# Display.net
KiCad netlist of a schematic drawn in Altium Designer
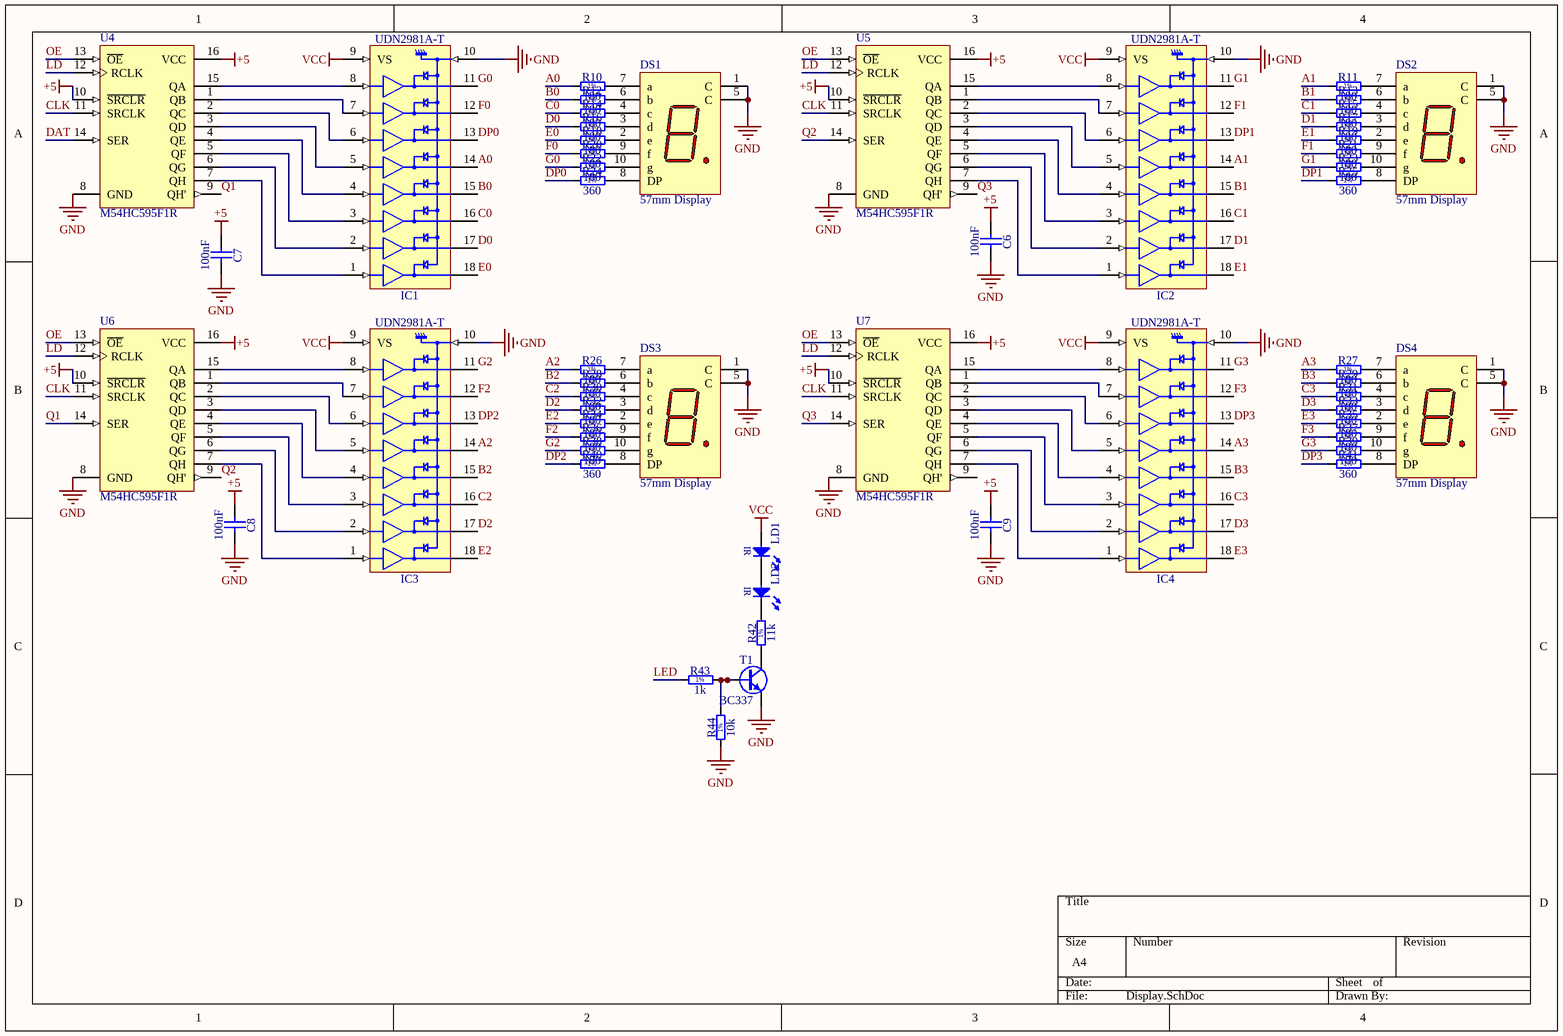
[diagram p0: Display.SchDoc]

(export (version "E")
  (design (tool "Eeschema 10.0.6"))
  (components
    (comp (ref "C6")
      (value "100nF")
      (footprint "CAPRR508-350X500X500")
      (description "Non-polarised capacitor")
      (fields
        (field (name "PART NUMBER") "CCR_100NF_50V_10%_X7R_508-350X500X500")
        (field (name "VOLTAGE") "50VDC")
        (field (name "AUTHOR") "CERN DEM JLC")
      )
      (libsource (lib "Capacitors") (part "Capacitor - non polarized"))
    )
    (comp (ref "C7")
      (value "100nF")
      (footprint "CAPRR508-350X500X500")
      (description "Non-polarised capacitor")
      (fields
        (field (name "PART NUMBER") "CCR_100NF_50V_10%_X7R_508-350X500X500")
        (field (name "VOLTAGE") "50VDC")
        (field (name "AUTHOR") "CERN DEM JLC")
      )
      (libsource (lib "Capacitors") (part "Capacitor - non polarized"))
    )
    (comp (ref "C8")
      (value "100nF")
      (footprint "CAPRR508-350X500X500")
      (description "Non-polarised capacitor")
      (fields
        (field (name "PART NUMBER") "CCR_100NF_50V_10%_X7R_508-350X500X500")
        (field (name "VOLTAGE") "50VDC")
        (field (name "AUTHOR") "CERN DEM JLC")
      )
      (libsource (lib "Capacitors") (part "Capacitor - non polarized"))
    )
    (comp (ref "C9")
      (value "100nF")
      (footprint "CAPRR508-350X500X500")
      (description "Non-polarised capacitor")
      (fields
        (field (name "PART NUMBER") "CCR_100NF_50V_10%_X7R_508-350X500X500")
        (field (name "VOLTAGE") "50VDC")
        (field (name "AUTHOR") "CERN DEM JLC")
      )
      (libsource (lib "Capacitors") (part "Capacitor - non polarized"))
    )
    (comp (ref "DS1")
      (value "57mm Display")
      (footprint "57mm 7 Segment")
      (libsource (lib "Tansa_Server_Schematic_Library") (part "57mm 2.3{dblquote} Display"))
    )
    (comp (ref "DS2")
      (value "57mm Display")
      (footprint "57mm 7 Segment")
      (libsource (lib "Tansa_Server_Schematic_Library") (part "57mm 2.3{dblquote} Display"))
    )
    (comp (ref "DS3")
      (value "57mm Display")
      (footprint "57mm 7 Segment")
      (libsource (lib "Tansa_Server_Schematic_Library") (part "57mm 2.3{dblquote} Display"))
    )
    (comp (ref "DS4")
      (value "57mm Display")
      (footprint "57mm 7 Segment")
      (libsource (lib "Tansa_Server_Schematic_Library") (part "57mm 2.3{dblquote} Display"))
    )
    (comp (ref "IC1")
      (value "UDN2981A-T")
      (footprint "DIP18-300")
      (description "8-Channel Source Drivers")
      (fields (field (name "MANUFACTURER") "ALLEGRO MICROSYSTEM") (field (name "AUTHOR") "CERN DEM JLC"))
      (libsource (lib "ICs And Semiconductors") (part "UDN2981"))
    )
    (comp (ref "IC2")
      (value "UDN2981A-T")
      (footprint "DIP18-300")
      (description "8-Channel Source Drivers")
      (fields (field (name "MANUFACTURER") "ALLEGRO MICROSYSTEM") (field (name "AUTHOR") "CERN DEM JLC"))
      (libsource (lib "ICs And Semiconductors") (part "UDN2981"))
    )
    (comp (ref "IC3")
      (value "UDN2981A-T")
      (footprint "DIP18-300")
      (description "8-Channel Source Drivers")
      (fields (field (name "MANUFACTURER") "ALLEGRO MICROSYSTEM") (field (name "AUTHOR") "CERN DEM JLC"))
      (libsource (lib "ICs And Semiconductors") (part "UDN2981"))
    )
    (comp (ref "IC4")
      (value "UDN2981A-T")
      (footprint "DIP18-300")
      (description "8-Channel Source Drivers")
      (fields (field (name "MANUFACTURER") "ALLEGRO MICROSYSTEM") (field (name "AUTHOR") "CERN DEM JLC"))
      (libsource (lib "ICs And Semiconductors") (part "UDN2981"))
    )
    (comp (ref "LD1")
      (value "IR")
      (footprint "LED_VISHAY_TSAL6200")
      (description "LED Infrared Emitting Diode 1C 2A")
      (fields
        (field (name "PART NUMBER") "LED_VISHAY_TSAL6200")
        (field (name "MANUFACTURER") "VISHAY SEMICONDUCTORS")
        (field (name "AUTHOR") "CERN DEM JMW")
      )
      (libsource (lib "ICs And Semiconductors") (part "LED IR 1C 2A"))
    )
    (comp (ref "LD2")
      (value "IR")
      (footprint "LED_VISHAY_TSAL6200")
      (description "LED Infrared Emitting Diode 1C 2A")
      (fields
        (field (name "PART NUMBER") "LED_VISHAY_TSAL6200")
        (field (name "MANUFACTURER") "VISHAY SEMICONDUCTORS")
        (field (name "AUTHOR") "CERN DEM JMW")
      )
      (libsource (lib "ICs And Semiconductors") (part "LED IR 1C 2A"))
    )
    (comp (ref "R10")
      (value "180")
      (footprint "RES1016-630X250")
      (description "Resistor - 1%")
      (fields
        (field (name "PART NUMBER") "RMF_180R_1%_0.6W_50PPM_1016-630X250")
        (field (name "POWER") "0.6W")
        (field (name "AUTHOR") "CERN DEM JLC")
      )
      (libsource (lib "Resistors") (part "Resistor - 1%"))
    )
    (comp (ref "R11")
      (value "180")
      (footprint "RES1016-630X250")
      (description "Resistor - 1%")
      (fields
        (field (name "PART NUMBER") "RMF_180R_1%_0.6W_50PPM_1016-630X250")
        (field (name "POWER") "0.6W")
        (field (name "AUTHOR") "CERN DEM JLC")
      )
      (libsource (lib "Resistors") (part "Resistor - 1%"))
    )
    (comp (ref "R12")
      (value "180")
      (footprint "RES1016-630X250")
      (description "Resistor - 1%")
      (fields
        (field (name "PART NUMBER") "RMF_180R_1%_0.6W_50PPM_1016-630X250")
        (field (name "POWER") "0.6W")
        (field (name "AUTHOR") "CERN DEM JLC")
      )
      (libsource (lib "Resistors") (part "Resistor - 1%"))
    )
    (comp (ref "R13")
      (value "180")
      (footprint "RES1016-630X250")
      (description "Resistor - 1%")
      (fields
        (field (name "PART NUMBER") "RMF_180R_1%_0.6W_50PPM_1016-630X250")
        (field (name "POWER") "0.6W")
        (field (name "AUTHOR") "CERN DEM JLC")
      )
      (libsource (lib "Resistors") (part "Resistor - 1%"))
    )
    (comp (ref "R14")
      (value "180")
      (footprint "RES1016-630X250")
      (description "Resistor - 1%")
      (fields
        (field (name "PART NUMBER") "RMF_180R_1%_0.6W_50PPM_1016-630X250")
        (field (name "POWER") "0.6W")
        (field (name "AUTHOR") "CERN DEM JLC")
      )
      (libsource (lib "Resistors") (part "Resistor - 1%"))
    )
    (comp (ref "R15")
      (value "180")
      (footprint "RES1016-630X250")
      (description "Resistor - 1%")
      (fields
        (field (name "PART NUMBER") "RMF_180R_1%_0.6W_50PPM_1016-630X250")
        (field (name "POWER") "0.6W")
        (field (name "AUTHOR") "CERN DEM JLC")
      )
      (libsource (lib "Resistors") (part "Resistor - 1%"))
    )
    (comp (ref "R16")
      (value "180")
      (footprint "RES1016-630X250")
      (description "Resistor - 1%")
      (fields
        (field (name "PART NUMBER") "RMF_180R_1%_0.6W_50PPM_1016-630X250")
        (field (name "POWER") "0.6W")
        (field (name "AUTHOR") "CERN DEM JLC")
      )
      (libsource (lib "Resistors") (part "Resistor - 1%"))
    )
    (comp (ref "R17")
      (value "180")
      (footprint "RES1016-630X250")
      (description "Resistor - 1%")
      (fields
        (field (name "PART NUMBER") "RMF_180R_1%_0.6W_50PPM_1016-630X250")
        (field (name "POWER") "0.6W")
        (field (name "AUTHOR") "CERN DEM JLC")
      )
      (libsource (lib "Resistors") (part "Resistor - 1%"))
    )
    (comp (ref "R18")
      (value "180")
      (footprint "RES1016-630X250")
      (description "Resistor - 1%")
      (fields
        (field (name "PART NUMBER") "RMF_180R_1%_0.6W_50PPM_1016-630X250")
        (field (name "POWER") "0.6W")
        (field (name "AUTHOR") "CERN DEM JLC")
      )
      (libsource (lib "Resistors") (part "Resistor - 1%"))
    )
    (comp (ref "R19")
      (value "180")
      (footprint "RES1016-630X250")
      (description "Resistor - 1%")
      (fields
        (field (name "PART NUMBER") "RMF_180R_1%_0.6W_50PPM_1016-630X250")
        (field (name "POWER") "0.6W")
        (field (name "AUTHOR") "CERN DEM JLC")
      )
      (libsource (lib "Resistors") (part "Resistor - 1%"))
    )
    (comp (ref "R20")
      (value "180")
      (footprint "RES1016-630X250")
      (description "Resistor - 1%")
      (fields
        (field (name "PART NUMBER") "RMF_180R_1%_0.6W_50PPM_1016-630X250")
        (field (name "POWER") "0.6W")
        (field (name "AUTHOR") "CERN DEM JLC")
      )
      (libsource (lib "Resistors") (part "Resistor - 1%"))
    )
    (comp (ref "R21")
      (value "180")
      (footprint "RES1016-630X250")
      (description "Resistor - 1%")
      (fields
        (field (name "PART NUMBER") "RMF_180R_1%_0.6W_50PPM_1016-630X250")
        (field (name "POWER") "0.6W")
        (field (name "AUTHOR") "CERN DEM JLC")
      )
      (libsource (lib "Resistors") (part "Resistor - 1%"))
    )
    (comp (ref "R22")
      (value "180")
      (footprint "RES1016-630X250")
      (description "Resistor - 1%")
      (fields
        (field (name "PART NUMBER") "RMF_180R_1%_0.6W_50PPM_1016-630X250")
        (field (name "POWER") "0.6W")
        (field (name "AUTHOR") "CERN DEM JLC")
      )
      (libsource (lib "Resistors") (part "Resistor - 1%"))
    )
    (comp (ref "R23")
      (value "180")
      (footprint "RES1016-630X250")
      (description "Resistor - 1%")
      (fields
        (field (name "PART NUMBER") "RMF_180R_1%_0.6W_50PPM_1016-630X250")
        (field (name "POWER") "0.6W")
        (field (name "AUTHOR") "CERN DEM JLC")
      )
      (libsource (lib "Resistors") (part "Resistor - 1%"))
    )
    (comp (ref "R24")
      (value "360")
      (footprint "RES1016-630X250")
      (description "Resistor - 1%")
      (fields
        (field (name "PART NUMBER") "RMF_360R_1%_0.6W_50PPM_1016-630X250")
        (field (name "POWER") "0.6W")
        (field (name "AUTHOR") "CERN DEM JLC")
      )
      (libsource (lib "Resistors") (part "Resistor - 1%"))
    )
    (comp (ref "R25")
      (value "360")
      (footprint "RES1016-630X250")
      (description "Resistor - 1%")
      (fields
        (field (name "PART NUMBER") "RMF_360R_1%_0.6W_50PPM_1016-630X250")
        (field (name "POWER") "0.6W")
        (field (name "AUTHOR") "CERN DEM JLC")
      )
      (libsource (lib "Resistors") (part "Resistor - 1%"))
    )
    (comp (ref "R26")
      (value "180")
      (footprint "RES1016-630X250")
      (description "Resistor - 1%")
      (fields
        (field (name "PART NUMBER") "RMF_180R_1%_0.6W_50PPM_1016-630X250")
        (field (name "POWER") "0.6W")
        (field (name "AUTHOR") "CERN DEM JLC")
      )
      (libsource (lib "Resistors") (part "Resistor - 1%"))
    )
    (comp (ref "R27")
      (value "180")
      (footprint "RES1016-630X250")
      (description "Resistor - 1%")
      (fields
        (field (name "PART NUMBER") "RMF_180R_1%_0.6W_50PPM_1016-630X250")
        (field (name "POWER") "0.6W")
        (field (name "AUTHOR") "CERN DEM JLC")
      )
      (libsource (lib "Resistors") (part "Resistor - 1%"))
    )
    (comp (ref "R28")
      (value "180")
      (footprint "RES1016-630X250")
      (description "Resistor - 1%")
      (fields
        (field (name "PART NUMBER") "RMF_180R_1%_0.6W_50PPM_1016-630X250")
        (field (name "POWER") "0.6W")
        (field (name "AUTHOR") "CERN DEM JLC")
      )
      (libsource (lib "Resistors") (part "Resistor - 1%"))
    )
    (comp (ref "R29")
      (value "180")
      (footprint "RES1016-630X250")
      (description "Resistor - 1%")
      (fields
        (field (name "PART NUMBER") "RMF_180R_1%_0.6W_50PPM_1016-630X250")
        (field (name "POWER") "0.6W")
        (field (name "AUTHOR") "CERN DEM JLC")
      )
      (libsource (lib "Resistors") (part "Resistor - 1%"))
    )
    (comp (ref "R30")
      (value "180")
      (footprint "RES1016-630X250")
      (description "Resistor - 1%")
      (fields
        (field (name "PART NUMBER") "RMF_180R_1%_0.6W_50PPM_1016-630X250")
        (field (name "POWER") "0.6W")
        (field (name "AUTHOR") "CERN DEM JLC")
      )
      (libsource (lib "Resistors") (part "Resistor - 1%"))
    )
    (comp (ref "R31")
      (value "180")
      (footprint "RES1016-630X250")
      (description "Resistor - 1%")
      (fields
        (field (name "PART NUMBER") "RMF_180R_1%_0.6W_50PPM_1016-630X250")
        (field (name "POWER") "0.6W")
        (field (name "AUTHOR") "CERN DEM JLC")
      )
      (libsource (lib "Resistors") (part "Resistor - 1%"))
    )
    (comp (ref "R32")
      (value "180")
      (footprint "RES1016-630X250")
      (description "Resistor - 1%")
      (fields
        (field (name "PART NUMBER") "RMF_180R_1%_0.6W_50PPM_1016-630X250")
        (field (name "POWER") "0.6W")
        (field (name "AUTHOR") "CERN DEM JLC")
      )
      (libsource (lib "Resistors") (part "Resistor - 1%"))
    )
    (comp (ref "R33")
      (value "180")
      (footprint "RES1016-630X250")
      (description "Resistor - 1%")
      (fields
        (field (name "PART NUMBER") "RMF_180R_1%_0.6W_50PPM_1016-630X250")
        (field (name "POWER") "0.6W")
        (field (name "AUTHOR") "CERN DEM JLC")
      )
      (libsource (lib "Resistors") (part "Resistor - 1%"))
    )
    (comp (ref "R34")
      (value "180")
      (footprint "RES1016-630X250")
      (description "Resistor - 1%")
      (fields
        (field (name "PART NUMBER") "RMF_180R_1%_0.6W_50PPM_1016-630X250")
        (field (name "POWER") "0.6W")
        (field (name "AUTHOR") "CERN DEM JLC")
      )
      (libsource (lib "Resistors") (part "Resistor - 1%"))
    )
    (comp (ref "R35")
      (value "180")
      (footprint "RES1016-630X250")
      (description "Resistor - 1%")
      (fields
        (field (name "PART NUMBER") "RMF_180R_1%_0.6W_50PPM_1016-630X250")
        (field (name "POWER") "0.6W")
        (field (name "AUTHOR") "CERN DEM JLC")
      )
      (libsource (lib "Resistors") (part "Resistor - 1%"))
    )
    (comp (ref "R36")
      (value "180")
      (footprint "RES1016-630X250")
      (description "Resistor - 1%")
      (fields
        (field (name "PART NUMBER") "RMF_180R_1%_0.6W_50PPM_1016-630X250")
        (field (name "POWER") "0.6W")
        (field (name "AUTHOR") "CERN DEM JLC")
      )
      (libsource (lib "Resistors") (part "Resistor - 1%"))
    )
    (comp (ref "R37")
      (value "180")
      (footprint "RES1016-630X250")
      (description "Resistor - 1%")
      (fields
        (field (name "PART NUMBER") "RMF_180R_1%_0.6W_50PPM_1016-630X250")
        (field (name "POWER") "0.6W")
        (field (name "AUTHOR") "CERN DEM JLC")
      )
      (libsource (lib "Resistors") (part "Resistor - 1%"))
    )
    (comp (ref "R38")
      (value "180")
      (footprint "RES1016-630X250")
      (description "Resistor - 1%")
      (fields
        (field (name "PART NUMBER") "RMF_180R_1%_0.6W_50PPM_1016-630X250")
        (field (name "POWER") "0.6W")
        (field (name "AUTHOR") "CERN DEM JLC")
      )
      (libsource (lib "Resistors") (part "Resistor - 1%"))
    )
    (comp (ref "R39")
      (value "180")
      (footprint "RES1016-630X250")
      (description "Resistor - 1%")
      (fields
        (field (name "PART NUMBER") "RMF_180R_1%_0.6W_50PPM_1016-630X250")
        (field (name "POWER") "0.6W")
        (field (name "AUTHOR") "CERN DEM JLC")
      )
      (libsource (lib "Resistors") (part "Resistor - 1%"))
    )
    (comp (ref "R40")
      (value "360")
      (footprint "RES1016-630X250")
      (description "Resistor - 1%")
      (fields
        (field (name "PART NUMBER") "RMF_360R_1%_0.6W_50PPM_1016-630X250")
        (field (name "POWER") "0.6W")
        (field (name "AUTHOR") "CERN DEM JLC")
      )
      (libsource (lib "Resistors") (part "Resistor - 1%"))
    )
    (comp (ref "R41")
      (value "360")
      (footprint "RES1016-630X250")
      (description "Resistor - 1%")
      (fields
        (field (name "PART NUMBER") "RMF_360R_1%_0.6W_50PPM_1016-630X250")
        (field (name "POWER") "0.6W")
        (field (name "AUTHOR") "CERN DEM JLC")
      )
      (libsource (lib "Resistors") (part "Resistor - 1%"))
    )
    (comp (ref "R42")
      (value "11k")
      (footprint "RES1016-630X250")
      (description "Resistor - 1%")
      (fields
        (field (name "PART NUMBER") "RMF_11K_1%_0.6W_50PPM_1016-630X250")
        (field (name "POWER") "0.6W")
        (field (name "AUTHOR") "CERN DEM JLC")
      )
      (libsource (lib "Resistors") (part "Resistor - 1%"))
    )
    (comp (ref "R43")
      (value "1k")
      (footprint "RES1016-630X250")
      (description "Resistor - 1%")
      (fields
        (field (name "PART NUMBER") "RMF_1K_1%_0.6W_50PPM_1016-630X250")
        (field (name "POWER") "0.6W")
        (field (name "AUTHOR") "CERN DEM JLC")
      )
      (libsource (lib "Resistors") (part "Resistor - 1%"))
    )
    (comp (ref "R44")
      (value "10k")
      (footprint "RES1016-630X250")
      (description "Resistor - 1%")
      (fields
        (field (name "PART NUMBER") "RMF_10K_1%_0.6W_50PPM_1016-630X250")
        (field (name "POWER") "0.6W")
        (field (name "AUTHOR") "CERN DEM JLC")
      )
      (libsource (lib "Resistors") (part "Resistor - 1%"))
    )
    (comp (ref "T1")
      (value "BC337")
      (footprint "TO-92AA-P254")
      (description "NPN Transistor")
      (fields (field (name "MANUFACTURER") "FAIRCHILD SEMICONDUCTOR") (field (name "AUTHOR") "CERN DEM JLC"))
      (libsource (lib "ICs And Semiconductors") (part "NPN C1 B2 E3"))
    )
    (comp (ref "U4")
      (value "M54HC595F1R")
      (footprint "DIP16")
      (description "8 Bit Shift Register with Output Latches (3 STATE)")
      (fields (field (name "PUBLISHER") "Altium Limited"))
      (libsource (lib "ST Logic Register") (part "M54HC595F1R"))
    )
    (comp (ref "U5")
      (value "M54HC595F1R")
      (footprint "DIP16")
      (description "8 Bit Shift Register with Output Latches (3 STATE)")
      (fields (field (name "PUBLISHER") "Altium Limited"))
      (libsource (lib "ST Logic Register") (part "M54HC595F1R"))
    )
    (comp (ref "U6")
      (value "M54HC595F1R")
      (footprint "DIP16")
      (description "8 Bit Shift Register with Output Latches (3 STATE)")
      (fields (field (name "PUBLISHER") "Altium Limited"))
      (libsource (lib "ST Logic Register") (part "M54HC595F1R"))
    )
    (comp (ref "U7")
      (value "M54HC595F1R")
      (footprint "DIP16")
      (description "8 Bit Shift Register with Output Latches (3 STATE)")
      (fields (field (name "PUBLISHER") "Altium Limited"))
      (libsource (lib "ST Logic Register") (part "M54HC595F1R"))
    )
  )
  (nets
    (net (code "1") (name "+5") (class "Default")
      (node (ref "C6") (pin "1") (pinfunction "1_1") (pintype "passive"))
      (node (ref "C7") (pin "1") (pinfunction "1_1") (pintype "passive"))
      (node (ref "C8") (pin "1") (pinfunction "1_1") (pintype "passive"))
      (node (ref "C9") (pin "1") (pinfunction "1_1") (pintype "passive"))
      (node (ref "U4") (pin "10") (pinfunction "~{SRCLR}_10") (pintype "input"))
      (node (ref "U4") (pin "16") (pinfunction "VCC_16") (pintype "power_in"))
      (node (ref "U5") (pin "10") (pinfunction "~{SRCLR}_10") (pintype "input"))
      (node (ref "U5") (pin "16") (pinfunction "VCC_16") (pintype "power_in"))
      (node (ref "U6") (pin "10") (pinfunction "~{SRCLR}_10") (pintype "input"))
      (node (ref "U6") (pin "16") (pinfunction "VCC_16") (pintype "power_in"))
      (node (ref "U7") (pin "10") (pinfunction "~{SRCLR}_10") (pintype "input"))
      (node (ref "U7") (pin "16") (pinfunction "VCC_16") (pintype "power_in"))
    )
    (net (code "2") (name "/A0") (class "Default")
      (node (ref "IC1") (pin "14") (pinfunction "O5_14") (pintype "open_collector"))
      (node (ref "R10") (pin "1") (pinfunction "1_1") (pintype "passive"))
    )
    (net (code "3") (name "/A1") (class "Default")
      (node (ref "IC2") (pin "14") (pinfunction "O5_14") (pintype "open_collector"))
      (node (ref "R11") (pin "1") (pinfunction "1_1") (pintype "passive"))
    )
    (net (code "4") (name "/A2") (class "Default")
      (node (ref "IC3") (pin "14") (pinfunction "O5_14") (pintype "open_collector"))
      (node (ref "R26") (pin "1") (pinfunction "1_1") (pintype "passive"))
    )
    (net (code "5") (name "/A3") (class "Default")
      (node (ref "IC4") (pin "14") (pinfunction "O5_14") (pintype "open_collector"))
      (node (ref "R27") (pin "1") (pinfunction "1_1") (pintype "passive"))
    )
    (net (code "6") (name "/B0") (class "Default")
      (node (ref "IC1") (pin "15") (pinfunction "O4_15") (pintype "open_collector"))
      (node (ref "R12") (pin "1") (pinfunction "1_1") (pintype "passive"))
    )
    (net (code "7") (name "/B1") (class "Default")
      (node (ref "IC2") (pin "15") (pinfunction "O4_15") (pintype "open_collector"))
      (node (ref "R13") (pin "1") (pinfunction "1_1") (pintype "passive"))
    )
    (net (code "8") (name "/B2") (class "Default")
      (node (ref "IC3") (pin "15") (pinfunction "O4_15") (pintype "open_collector"))
      (node (ref "R28") (pin "1") (pinfunction "1_1") (pintype "passive"))
    )
    (net (code "9") (name "/B3") (class "Default")
      (node (ref "IC4") (pin "15") (pinfunction "O4_15") (pintype "open_collector"))
      (node (ref "R29") (pin "1") (pinfunction "1_1") (pintype "passive"))
    )
    (net (code "10") (name "/C0") (class "Default")
      (node (ref "IC1") (pin "16") (pinfunction "O3_16") (pintype "open_collector"))
      (node (ref "R14") (pin "1") (pinfunction "1_1") (pintype "passive"))
    )
    (net (code "11") (name "/C1") (class "Default")
      (node (ref "IC2") (pin "16") (pinfunction "O3_16") (pintype "open_collector"))
      (node (ref "R15") (pin "1") (pinfunction "1_1") (pintype "passive"))
    )
    (net (code "12") (name "/C2") (class "Default")
      (node (ref "IC3") (pin "16") (pinfunction "O3_16") (pintype "open_collector"))
      (node (ref "R30") (pin "1") (pinfunction "1_1") (pintype "passive"))
    )
    (net (code "13") (name "/C3") (class "Default")
      (node (ref "IC4") (pin "16") (pinfunction "O3_16") (pintype "open_collector"))
      (node (ref "R31") (pin "1") (pinfunction "1_1") (pintype "passive"))
    )
    (net (code "14") (name "/CLK") (class "Default")
      (node (ref "U4") (pin "11") (pinfunction "SRCLK_11") (pintype "input"))
      (node (ref "U5") (pin "11") (pinfunction "SRCLK_11") (pintype "input"))
      (node (ref "U6") (pin "11") (pinfunction "SRCLK_11") (pintype "input"))
      (node (ref "U7") (pin "11") (pinfunction "SRCLK_11") (pintype "input"))
    )
    (net (code "15") (name "/D0") (class "Default")
      (node (ref "IC1") (pin "17") (pinfunction "O2_17") (pintype "open_collector"))
      (node (ref "R16") (pin "1") (pinfunction "1_1") (pintype "passive"))
    )
    (net (code "16") (name "/D1") (class "Default")
      (node (ref "IC2") (pin "17") (pinfunction "O2_17") (pintype "open_collector"))
      (node (ref "R17") (pin "1") (pinfunction "1_1") (pintype "passive"))
    )
    (net (code "17") (name "/D2") (class "Default")
      (node (ref "IC3") (pin "17") (pinfunction "O2_17") (pintype "open_collector"))
      (node (ref "R32") (pin "1") (pinfunction "1_1") (pintype "passive"))
    )
    (net (code "18") (name "/D3") (class "Default")
      (node (ref "IC4") (pin "17") (pinfunction "O2_17") (pintype "open_collector"))
      (node (ref "R33") (pin "1") (pinfunction "1_1") (pintype "passive"))
    )
    (net (code "19") (name "/DAT") (class "Default")
      (node (ref "U4") (pin "14") (pinfunction "SER_14") (pintype "input"))
    )
    (net (code "20") (name "/DP0") (class "Default")
      (node (ref "IC1") (pin "13") (pinfunction "O6_13") (pintype "open_collector"))
      (node (ref "R24") (pin "1") (pinfunction "1_1") (pintype "passive"))
    )
    (net (code "21") (name "/DP1") (class "Default")
      (node (ref "IC2") (pin "13") (pinfunction "O6_13") (pintype "open_collector"))
      (node (ref "R25") (pin "1") (pinfunction "1_1") (pintype "passive"))
    )
    (net (code "22") (name "/DP2") (class "Default")
      (node (ref "IC3") (pin "13") (pinfunction "O6_13") (pintype "open_collector"))
      (node (ref "R40") (pin "1") (pinfunction "1_1") (pintype "passive"))
    )
    (net (code "23") (name "/DP3") (class "Default")
      (node (ref "IC4") (pin "13") (pinfunction "O6_13") (pintype "open_collector"))
      (node (ref "R41") (pin "1") (pinfunction "1_1") (pintype "passive"))
    )
    (net (code "24") (name "/E0") (class "Default")
      (node (ref "IC1") (pin "18") (pinfunction "O1_18") (pintype "open_collector"))
      (node (ref "R18") (pin "1") (pinfunction "1_1") (pintype "passive"))
    )
    (net (code "25") (name "/E1") (class "Default")
      (node (ref "IC2") (pin "18") (pinfunction "O1_18") (pintype "open_collector"))
      (node (ref "R19") (pin "1") (pinfunction "1_1") (pintype "passive"))
    )
    (net (code "26") (name "/E2") (class "Default")
      (node (ref "IC3") (pin "18") (pinfunction "O1_18") (pintype "open_collector"))
      (node (ref "R34") (pin "1") (pinfunction "1_1") (pintype "passive"))
    )
    (net (code "27") (name "/E3") (class "Default")
      (node (ref "IC4") (pin "18") (pinfunction "O1_18") (pintype "open_collector"))
      (node (ref "R35") (pin "1") (pinfunction "1_1") (pintype "passive"))
    )
    (net (code "28") (name "/F0") (class "Default")
      (node (ref "IC1") (pin "12") (pinfunction "O7_12") (pintype "open_collector"))
      (node (ref "R20") (pin "1") (pinfunction "1_1") (pintype "passive"))
    )
    (net (code "29") (name "/F1") (class "Default")
      (node (ref "IC2") (pin "12") (pinfunction "O7_12") (pintype "open_collector"))
      (node (ref "R21") (pin "1") (pinfunction "1_1") (pintype "passive"))
    )
    (net (code "30") (name "/F2") (class "Default")
      (node (ref "IC3") (pin "12") (pinfunction "O7_12") (pintype "open_collector"))
      (node (ref "R36") (pin "1") (pinfunction "1_1") (pintype "passive"))
    )
    (net (code "31") (name "/F3") (class "Default")
      (node (ref "IC4") (pin "12") (pinfunction "O7_12") (pintype "open_collector"))
      (node (ref "R37") (pin "1") (pinfunction "1_1") (pintype "passive"))
    )
    (net (code "32") (name "/G0") (class "Default")
      (node (ref "IC1") (pin "11") (pinfunction "O8_11") (pintype "open_collector"))
      (node (ref "R22") (pin "1") (pinfunction "1_1") (pintype "passive"))
    )
    (net (code "33") (name "/G1") (class "Default")
      (node (ref "IC2") (pin "11") (pinfunction "O8_11") (pintype "open_collector"))
      (node (ref "R23") (pin "1") (pinfunction "1_1") (pintype "passive"))
    )
    (net (code "34") (name "/G2") (class "Default")
      (node (ref "IC3") (pin "11") (pinfunction "O8_11") (pintype "open_collector"))
      (node (ref "R38") (pin "1") (pinfunction "1_1") (pintype "passive"))
    )
    (net (code "35") (name "/G3") (class "Default")
      (node (ref "IC4") (pin "11") (pinfunction "O8_11") (pintype "open_collector"))
      (node (ref "R39") (pin "1") (pinfunction "1_1") (pintype "passive"))
    )
    (net (code "36") (name "/LD") (class "Default")
      (node (ref "U4") (pin "12") (pinfunction "RCLK_12") (pintype "input"))
      (node (ref "U5") (pin "12") (pinfunction "RCLK_12") (pintype "input"))
      (node (ref "U6") (pin "12") (pinfunction "RCLK_12") (pintype "input"))
      (node (ref "U7") (pin "12") (pinfunction "RCLK_12") (pintype "input"))
    )
    (net (code "37") (name "/LED") (class "Default")
      (node (ref "R43") (pin "1") (pinfunction "1_1") (pintype "passive"))
    )
    (net (code "38") (name "/OE") (class "Default")
      (node (ref "U4") (pin "13") (pinfunction "~{OE}_13") (pintype "input"))
      (node (ref "U5") (pin "13") (pinfunction "~{OE}_13") (pintype "input"))
      (node (ref "U6") (pin "13") (pinfunction "~{OE}_13") (pintype "input"))
      (node (ref "U7") (pin "13") (pinfunction "~{OE}_13") (pintype "input"))
    )
    (net (code "39") (name "/Q1") (class "Default")
      (node (ref "U4") (pin "9") (pinfunction "QH'_9") (pintype "output"))
      (node (ref "U6") (pin "14") (pinfunction "SER_14") (pintype "input"))
    )
    (net (code "40") (name "/Q2") (class "Default")
      (node (ref "U5") (pin "14") (pinfunction "SER_14") (pintype "input"))
      (node (ref "U6") (pin "9") (pinfunction "QH'_9") (pintype "output"))
    )
    (net (code "41") (name "/Q3") (class "Default")
      (node (ref "U5") (pin "9") (pinfunction "QH'_9") (pintype "output"))
      (node (ref "U7") (pin "14") (pinfunction "SER_14") (pintype "input"))
    )
    (net (code "42") (name "GND") (class "Default")
      (node (ref "C6") (pin "2") (pinfunction "2_2") (pintype "passive"))
      (node (ref "C7") (pin "2") (pinfunction "2_2") (pintype "passive"))
      (node (ref "C8") (pin "2") (pinfunction "2_2") (pintype "passive"))
      (node (ref "C9") (pin "2") (pinfunction "2_2") (pintype "passive"))
      (node (ref "DS1") (pin "1") (pinfunction "C_1") (pintype "passive"))
      (node (ref "DS1") (pin "5") (pinfunction "C_5") (pintype "passive"))
      (node (ref "DS2") (pin "1") (pinfunction "C_1") (pintype "passive"))
      (node (ref "DS2") (pin "5") (pinfunction "C_5") (pintype "passive"))
      (node (ref "DS3") (pin "1") (pinfunction "C_1") (pintype "passive"))
      (node (ref "DS3") (pin "5") (pinfunction "C_5") (pintype "passive"))
      (node (ref "DS4") (pin "1") (pinfunction "C_1") (pintype "passive"))
      (node (ref "DS4") (pin "5") (pinfunction "C_5") (pintype "passive"))
      (node (ref "IC1") (pin "10") (pinfunction "COM_10") (pintype "input"))
      (node (ref "IC2") (pin "10") (pinfunction "COM_10") (pintype "input"))
      (node (ref "IC3") (pin "10") (pinfunction "COM_10") (pintype "input"))
      (node (ref "IC4") (pin "10") (pinfunction "COM_10") (pintype "input"))
      (node (ref "R44") (pin "1") (pinfunction "1_1") (pintype "passive"))
      (node (ref "T1") (pin "3") (pinfunction "E_3") (pintype "passive"))
      (node (ref "U4") (pin "8") (pinfunction "GND_8") (pintype "power_in"))
      (node (ref "U5") (pin "8") (pinfunction "GND_8") (pintype "power_in"))
      (node (ref "U6") (pin "8") (pinfunction "GND_8") (pintype "power_in"))
      (node (ref "U7") (pin "8") (pinfunction "GND_8") (pintype "power_in"))
    )
    (net (code "43") (name "Net-(DS1-DP)") (class "Default")
      (node (ref "DS1") (pin "8") (pinfunction "DP_8") (pintype "passive"))
      (node (ref "R24") (pin "2") (pinfunction "2_2") (pintype "passive"))
    )
    (net (code "44") (name "Net-(DS1-a)") (class "Default")
      (node (ref "DS1") (pin "7") (pinfunction "a_7") (pintype "passive"))
      (node (ref "R10") (pin "2") (pinfunction "2_2") (pintype "passive"))
    )
    (net (code "45") (name "Net-(DS1-b)") (class "Default")
      (node (ref "DS1") (pin "6") (pinfunction "b_6") (pintype "passive"))
      (node (ref "R12") (pin "2") (pinfunction "2_2") (pintype "passive"))
    )
    (net (code "46") (name "Net-(DS1-c)") (class "Default")
      (node (ref "DS1") (pin "4") (pinfunction "c_4") (pintype "passive"))
      (node (ref "R14") (pin "2") (pinfunction "2_2") (pintype "passive"))
    )
    (net (code "47") (name "Net-(DS1-d)") (class "Default")
      (node (ref "DS1") (pin "3") (pinfunction "d_3") (pintype "passive"))
      (node (ref "R16") (pin "2") (pinfunction "2_2") (pintype "passive"))
    )
    (net (code "48") (name "Net-(DS1-e)") (class "Default")
      (node (ref "DS1") (pin "2") (pinfunction "e_2") (pintype "passive"))
      (node (ref "R18") (pin "2") (pinfunction "2_2") (pintype "passive"))
    )
    (net (code "49") (name "Net-(DS1-f)") (class "Default")
      (node (ref "DS1") (pin "9") (pinfunction "f_9") (pintype "passive"))
      (node (ref "R20") (pin "2") (pinfunction "2_2") (pintype "passive"))
    )
    (net (code "50") (name "Net-(DS1-g)") (class "Default")
      (node (ref "DS1") (pin "10") (pinfunction "g_10") (pintype "passive"))
      (node (ref "R22") (pin "2") (pinfunction "2_2") (pintype "passive"))
    )
    (net (code "51") (name "Net-(DS2-DP)") (class "Default")
      (node (ref "DS2") (pin "8") (pinfunction "DP_8") (pintype "passive"))
      (node (ref "R25") (pin "2") (pinfunction "2_2") (pintype "passive"))
    )
    (net (code "52") (name "Net-(DS2-a)") (class "Default")
      (node (ref "DS2") (pin "7") (pinfunction "a_7") (pintype "passive"))
      (node (ref "R11") (pin "2") (pinfunction "2_2") (pintype "passive"))
    )
    (net (code "53") (name "Net-(DS2-b)") (class "Default")
      (node (ref "DS2") (pin "6") (pinfunction "b_6") (pintype "passive"))
      (node (ref "R13") (pin "2") (pinfunction "2_2") (pintype "passive"))
    )
    (net (code "54") (name "Net-(DS2-c)") (class "Default")
      (node (ref "DS2") (pin "4") (pinfunction "c_4") (pintype "passive"))
      (node (ref "R15") (pin "2") (pinfunction "2_2") (pintype "passive"))
    )
    (net (code "55") (name "Net-(DS2-d)") (class "Default")
      (node (ref "DS2") (pin "3") (pinfunction "d_3") (pintype "passive"))
      (node (ref "R17") (pin "2") (pinfunction "2_2") (pintype "passive"))
    )
    (net (code "56") (name "Net-(DS2-e)") (class "Default")
      (node (ref "DS2") (pin "2") (pinfunction "e_2") (pintype "passive"))
      (node (ref "R19") (pin "2") (pinfunction "2_2") (pintype "passive"))
    )
    (net (code "57") (name "Net-(DS2-f)") (class "Default")
      (node (ref "DS2") (pin "9") (pinfunction "f_9") (pintype "passive"))
      (node (ref "R21") (pin "2") (pinfunction "2_2") (pintype "passive"))
    )
    (net (code "58") (name "Net-(DS2-g)") (class "Default")
      (node (ref "DS2") (pin "10") (pinfunction "g_10") (pintype "passive"))
      (node (ref "R23") (pin "2") (pinfunction "2_2") (pintype "passive"))
    )
    (net (code "59") (name "Net-(DS3-DP)") (class "Default")
      (node (ref "DS3") (pin "8") (pinfunction "DP_8") (pintype "passive"))
      (node (ref "R40") (pin "2") (pinfunction "2_2") (pintype "passive"))
    )
    (net (code "60") (name "Net-(DS3-a)") (class "Default")
      (node (ref "DS3") (pin "7") (pinfunction "a_7") (pintype "passive"))
      (node (ref "R26") (pin "2") (pinfunction "2_2") (pintype "passive"))
    )
    (net (code "61") (name "Net-(DS3-b)") (class "Default")
      (node (ref "DS3") (pin "6") (pinfunction "b_6") (pintype "passive"))
      (node (ref "R28") (pin "2") (pinfunction "2_2") (pintype "passive"))
    )
    (net (code "62") (name "Net-(DS3-c)") (class "Default")
      (node (ref "DS3") (pin "4") (pinfunction "c_4") (pintype "passive"))
      (node (ref "R30") (pin "2") (pinfunction "2_2") (pintype "passive"))
    )
    (net (code "63") (name "Net-(DS3-d)") (class "Default")
      (node (ref "DS3") (pin "3") (pinfunction "d_3") (pintype "passive"))
      (node (ref "R32") (pin "2") (pinfunction "2_2") (pintype "passive"))
    )
    (net (code "64") (name "Net-(DS3-e)") (class "Default")
      (node (ref "DS3") (pin "2") (pinfunction "e_2") (pintype "passive"))
      (node (ref "R34") (pin "2") (pinfunction "2_2") (pintype "passive"))
    )
    (net (code "65") (name "Net-(DS3-f)") (class "Default")
      (node (ref "DS3") (pin "9") (pinfunction "f_9") (pintype "passive"))
      (node (ref "R36") (pin "2") (pinfunction "2_2") (pintype "passive"))
    )
    (net (code "66") (name "Net-(DS3-g)") (class "Default")
      (node (ref "DS3") (pin "10") (pinfunction "g_10") (pintype "passive"))
      (node (ref "R38") (pin "2") (pinfunction "2_2") (pintype "passive"))
    )
    (net (code "67") (name "Net-(DS4-DP)") (class "Default")
      (node (ref "DS4") (pin "8") (pinfunction "DP_8") (pintype "passive"))
      (node (ref "R41") (pin "2") (pinfunction "2_2") (pintype "passive"))
    )
    (net (code "68") (name "Net-(DS4-a)") (class "Default")
      (node (ref "DS4") (pin "7") (pinfunction "a_7") (pintype "passive"))
      (node (ref "R27") (pin "2") (pinfunction "2_2") (pintype "passive"))
    )
    (net (code "69") (name "Net-(DS4-b)") (class "Default")
      (node (ref "DS4") (pin "6") (pinfunction "b_6") (pintype "passive"))
      (node (ref "R29") (pin "2") (pinfunction "2_2") (pintype "passive"))
    )
    (net (code "70") (name "Net-(DS4-c)") (class "Default")
      (node (ref "DS4") (pin "4") (pinfunction "c_4") (pintype "passive"))
      (node (ref "R31") (pin "2") (pinfunction "2_2") (pintype "passive"))
    )
    (net (code "71") (name "Net-(DS4-d)") (class "Default")
      (node (ref "DS4") (pin "3") (pinfunction "d_3") (pintype "passive"))
      (node (ref "R33") (pin "2") (pinfunction "2_2") (pintype "passive"))
    )
    (net (code "72") (name "Net-(DS4-e)") (class "Default")
      (node (ref "DS4") (pin "2") (pinfunction "e_2") (pintype "passive"))
      (node (ref "R35") (pin "2") (pinfunction "2_2") (pintype "passive"))
    )
    (net (code "73") (name "Net-(DS4-f)") (class "Default")
      (node (ref "DS4") (pin "9") (pinfunction "f_9") (pintype "passive"))
      (node (ref "R37") (pin "2") (pinfunction "2_2") (pintype "passive"))
    )
    (net (code "74") (name "Net-(DS4-g)") (class "Default")
      (node (ref "DS4") (pin "10") (pinfunction "g_10") (pintype "passive"))
      (node (ref "R39") (pin "2") (pinfunction "2_2") (pintype "passive"))
    )
    (net (code "75") (name "Net-(IC1-I1)") (class "Default")
      (node (ref "IC1") (pin "1") (pinfunction "I1_1") (pintype "input"))
      (node (ref "U4") (pin "7") (pinfunction "QH_7") (pintype "tri_state"))
    )
    (net (code "76") (name "Net-(IC1-I2)") (class "Default")
      (node (ref "IC1") (pin "2") (pinfunction "I2_2") (pintype "input"))
      (node (ref "U4") (pin "6") (pinfunction "QG_6") (pintype "tri_state"))
    )
    (net (code "77") (name "Net-(IC1-I3)") (class "Default")
      (node (ref "IC1") (pin "3") (pinfunction "I3_3") (pintype "input"))
      (node (ref "U4") (pin "5") (pinfunction "QF_5") (pintype "tri_state"))
    )
    (net (code "78") (name "Net-(IC1-I4)") (class "Default")
      (node (ref "IC1") (pin "4") (pinfunction "I4_4") (pintype "input"))
      (node (ref "U4") (pin "4") (pinfunction "QE_4") (pintype "tri_state"))
    )
    (net (code "79") (name "Net-(IC1-I5)") (class "Default")
      (node (ref "IC1") (pin "5") (pinfunction "I5_5") (pintype "input"))
      (node (ref "U4") (pin "3") (pinfunction "QD_3") (pintype "tri_state"))
    )
    (net (code "80") (name "Net-(IC1-I6)") (class "Default")
      (node (ref "IC1") (pin "6") (pinfunction "I6_6") (pintype "input"))
      (node (ref "U4") (pin "2") (pinfunction "QC_2") (pintype "tri_state"))
    )
    (net (code "81") (name "Net-(IC1-I7)") (class "Default")
      (node (ref "IC1") (pin "7") (pinfunction "I7_7") (pintype "input"))
      (node (ref "U4") (pin "1") (pinfunction "QB_1") (pintype "tri_state"))
    )
    (net (code "82") (name "Net-(IC1-I8)") (class "Default")
      (node (ref "IC1") (pin "8") (pinfunction "I8_8") (pintype "input"))
      (node (ref "U4") (pin "15") (pinfunction "QA_15") (pintype "tri_state"))
    )
    (net (code "83") (name "Net-(IC2-I1)") (class "Default")
      (node (ref "IC2") (pin "1") (pinfunction "I1_1") (pintype "input"))
      (node (ref "U5") (pin "7") (pinfunction "QH_7") (pintype "tri_state"))
    )
    (net (code "84") (name "Net-(IC2-I2)") (class "Default")
      (node (ref "IC2") (pin "2") (pinfunction "I2_2") (pintype "input"))
      (node (ref "U5") (pin "6") (pinfunction "QG_6") (pintype "tri_state"))
    )
    (net (code "85") (name "Net-(IC2-I3)") (class "Default")
      (node (ref "IC2") (pin "3") (pinfunction "I3_3") (pintype "input"))
      (node (ref "U5") (pin "5") (pinfunction "QF_5") (pintype "tri_state"))
    )
    (net (code "86") (name "Net-(IC2-I4)") (class "Default")
      (node (ref "IC2") (pin "4") (pinfunction "I4_4") (pintype "input"))
      (node (ref "U5") (pin "4") (pinfunction "QE_4") (pintype "tri_state"))
    )
    (net (code "87") (name "Net-(IC2-I5)") (class "Default")
      (node (ref "IC2") (pin "5") (pinfunction "I5_5") (pintype "input"))
      (node (ref "U5") (pin "3") (pinfunction "QD_3") (pintype "tri_state"))
    )
    (net (code "88") (name "Net-(IC2-I6)") (class "Default")
      (node (ref "IC2") (pin "6") (pinfunction "I6_6") (pintype "input"))
      (node (ref "U5") (pin "2") (pinfunction "QC_2") (pintype "tri_state"))
    )
    (net (code "89") (name "Net-(IC2-I7)") (class "Default")
      (node (ref "IC2") (pin "7") (pinfunction "I7_7") (pintype "input"))
      (node (ref "U5") (pin "1") (pinfunction "QB_1") (pintype "tri_state"))
    )
    (net (code "90") (name "Net-(IC2-I8)") (class "Default")
      (node (ref "IC2") (pin "8") (pinfunction "I8_8") (pintype "input"))
      (node (ref "U5") (pin "15") (pinfunction "QA_15") (pintype "tri_state"))
    )
    (net (code "91") (name "Net-(IC3-I1)") (class "Default")
      (node (ref "IC3") (pin "1") (pinfunction "I1_1") (pintype "input"))
      (node (ref "U6") (pin "7") (pinfunction "QH_7") (pintype "tri_state"))
    )
    (net (code "92") (name "Net-(IC3-I2)") (class "Default")
      (node (ref "IC3") (pin "2") (pinfunction "I2_2") (pintype "input"))
      (node (ref "U6") (pin "6") (pinfunction "QG_6") (pintype "tri_state"))
    )
    (net (code "93") (name "Net-(IC3-I3)") (class "Default")
      (node (ref "IC3") (pin "3") (pinfunction "I3_3") (pintype "input"))
      (node (ref "U6") (pin "5") (pinfunction "QF_5") (pintype "tri_state"))
    )
    (net (code "94") (name "Net-(IC3-I4)") (class "Default")
      (node (ref "IC3") (pin "4") (pinfunction "I4_4") (pintype "input"))
      (node (ref "U6") (pin "4") (pinfunction "QE_4") (pintype "tri_state"))
    )
    (net (code "95") (name "Net-(IC3-I5)") (class "Default")
      (node (ref "IC3") (pin "5") (pinfunction "I5_5") (pintype "input"))
      (node (ref "U6") (pin "3") (pinfunction "QD_3") (pintype "tri_state"))
    )
    (net (code "96") (name "Net-(IC3-I6)") (class "Default")
      (node (ref "IC3") (pin "6") (pinfunction "I6_6") (pintype "input"))
      (node (ref "U6") (pin "2") (pinfunction "QC_2") (pintype "tri_state"))
    )
    (net (code "97") (name "Net-(IC3-I7)") (class "Default")
      (node (ref "IC3") (pin "7") (pinfunction "I7_7") (pintype "input"))
      (node (ref "U6") (pin "1") (pinfunction "QB_1") (pintype "tri_state"))
    )
    (net (code "98") (name "Net-(IC3-I8)") (class "Default")
      (node (ref "IC3") (pin "8") (pinfunction "I8_8") (pintype "input"))
      (node (ref "U6") (pin "15") (pinfunction "QA_15") (pintype "tri_state"))
    )
    (net (code "99") (name "Net-(IC4-I1)") (class "Default")
      (node (ref "IC4") (pin "1") (pinfunction "I1_1") (pintype "input"))
      (node (ref "U7") (pin "7") (pinfunction "QH_7") (pintype "tri_state"))
    )
    (net (code "100") (name "Net-(IC4-I2)") (class "Default")
      (node (ref "IC4") (pin "2") (pinfunction "I2_2") (pintype "input"))
      (node (ref "U7") (pin "6") (pinfunction "QG_6") (pintype "tri_state"))
    )
    (net (code "101") (name "Net-(IC4-I3)") (class "Default")
      (node (ref "IC4") (pin "3") (pinfunction "I3_3") (pintype "input"))
      (node (ref "U7") (pin "5") (pinfunction "QF_5") (pintype "tri_state"))
    )
    (net (code "102") (name "Net-(IC4-I4)") (class "Default")
      (node (ref "IC4") (pin "4") (pinfunction "I4_4") (pintype "input"))
      (node (ref "U7") (pin "4") (pinfunction "QE_4") (pintype "tri_state"))
    )
    (net (code "103") (name "Net-(IC4-I5)") (class "Default")
      (node (ref "IC4") (pin "5") (pinfunction "I5_5") (pintype "input"))
      (node (ref "U7") (pin "3") (pinfunction "QD_3") (pintype "tri_state"))
    )
    (net (code "104") (name "Net-(IC4-I6)") (class "Default")
      (node (ref "IC4") (pin "6") (pinfunction "I6_6") (pintype "input"))
      (node (ref "U7") (pin "2") (pinfunction "QC_2") (pintype "tri_state"))
    )
    (net (code "105") (name "Net-(IC4-I7)") (class "Default")
      (node (ref "IC4") (pin "7") (pinfunction "I7_7") (pintype "input"))
      (node (ref "U7") (pin "1") (pinfunction "QB_1") (pintype "tri_state"))
    )
    (net (code "106") (name "Net-(IC4-I8)") (class "Default")
      (node (ref "IC4") (pin "8") (pinfunction "I8_8") (pintype "input"))
      (node (ref "U7") (pin "15") (pinfunction "QA_15") (pintype "tri_state"))
    )
    (net (code "107") (name "Net-(LD1-C)") (class "Default")
      (node (ref "LD1") (pin "1") (pinfunction "C_1") (pintype "passive"))
      (node (ref "LD2") (pin "2") (pinfunction "A_2") (pintype "passive"))
    )
    (net (code "108") (name "Net-(LD2-C)") (class "Default")
      (node (ref "LD2") (pin "1") (pinfunction "C_1") (pintype "passive"))
      (node (ref "R42") (pin "2") (pinfunction "2_2") (pintype "passive"))
    )
    (net (code "109") (name "Net-(T1-B)") (class "Default")
      (node (ref "R43") (pin "2") (pinfunction "2_2") (pintype "passive"))
      (node (ref "R44") (pin "2") (pinfunction "2_2") (pintype "passive"))
      (node (ref "T1") (pin "2") (pinfunction "B_2") (pintype "passive"))
    )
    (net (code "110") (name "Net-(T1-C)") (class "Default")
      (node (ref "R42") (pin "1") (pinfunction "1_1") (pintype "passive"))
      (node (ref "T1") (pin "1") (pinfunction "C_1") (pintype "passive"))
    )
    (net (code "111") (name "VCC") (class "Default")
      (node (ref "IC1") (pin "9") (pinfunction "VS_9") (pintype "input"))
      (node (ref "IC2") (pin "9") (pinfunction "VS_9") (pintype "input"))
      (node (ref "IC3") (pin "9") (pinfunction "VS_9") (pintype "input"))
      (node (ref "IC4") (pin "9") (pinfunction "VS_9") (pintype "input"))
      (node (ref "LD1") (pin "2") (pinfunction "A_2") (pintype "passive"))
    )
    (net (code "112") (name "unconnected-(U7-QH'-Pad9)") (class "Default")
      (node (ref "U7") (pin "9") (pinfunction "QH'_9") (pintype "output"))
    )
  )
)
